# T14_SuperDuper_V_002.net
KiCad netlist of a schematic drawn in EAGLE
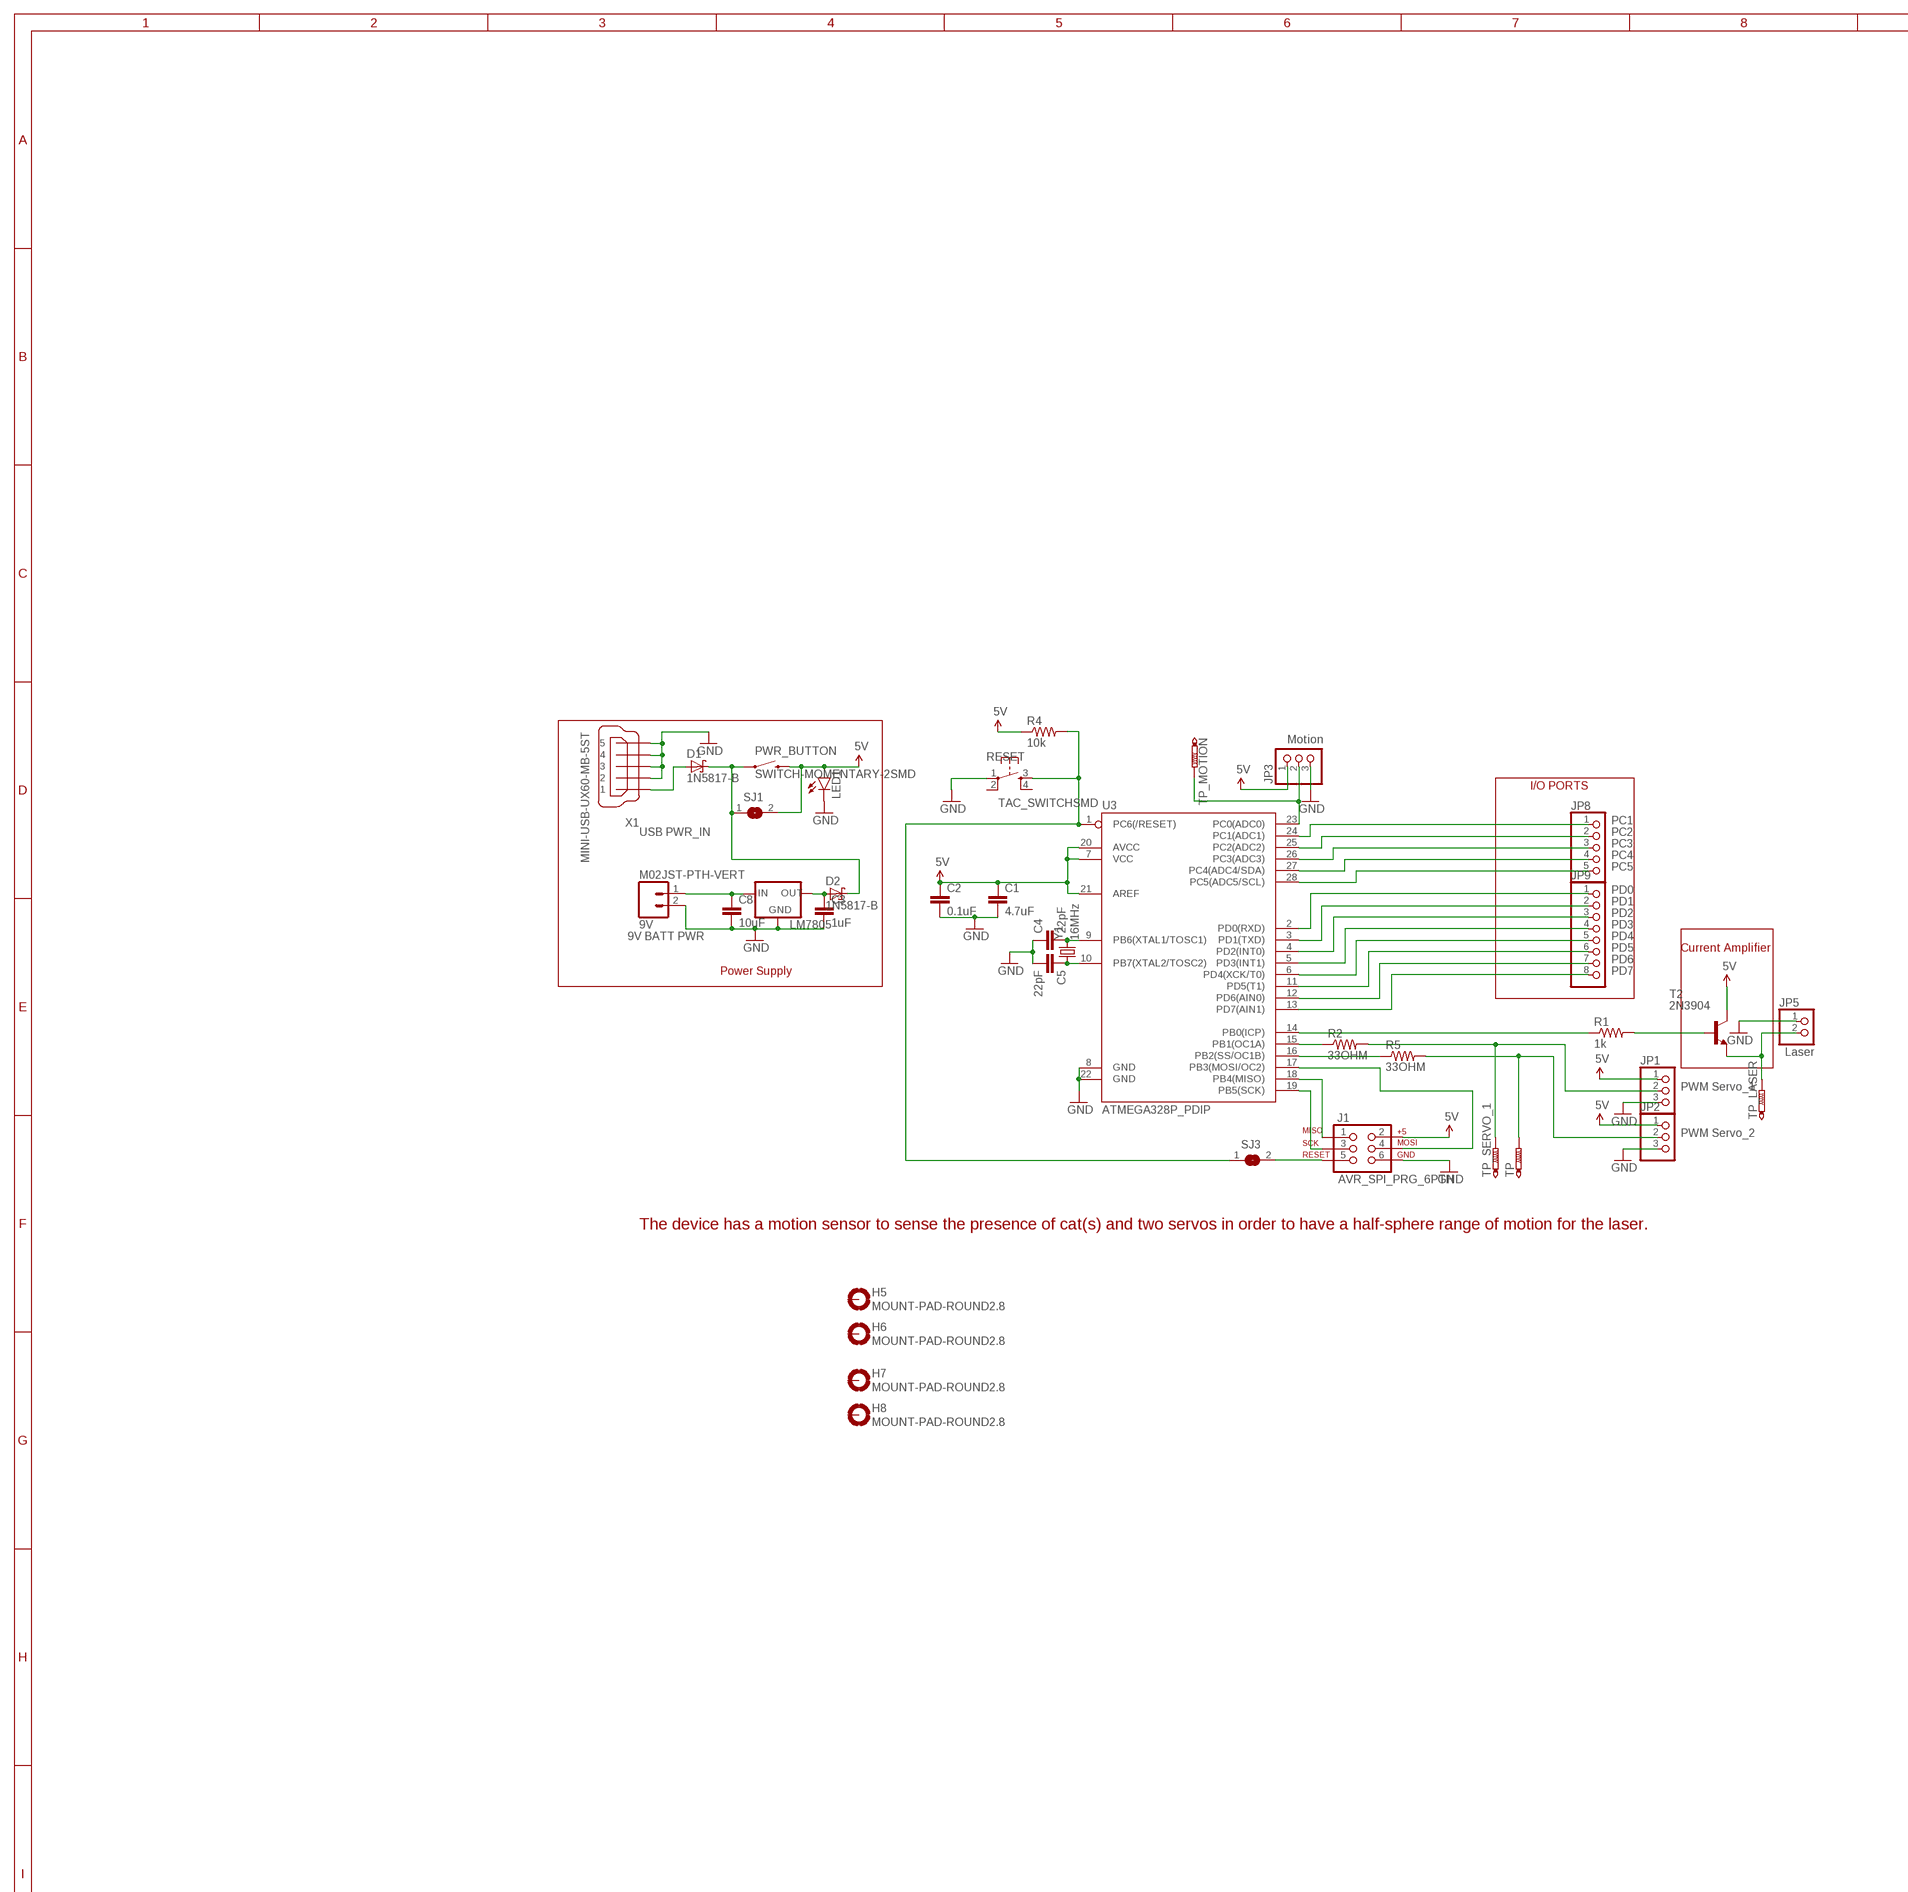
[diagram p0: schematic, sheet 1, part 1 of 2]
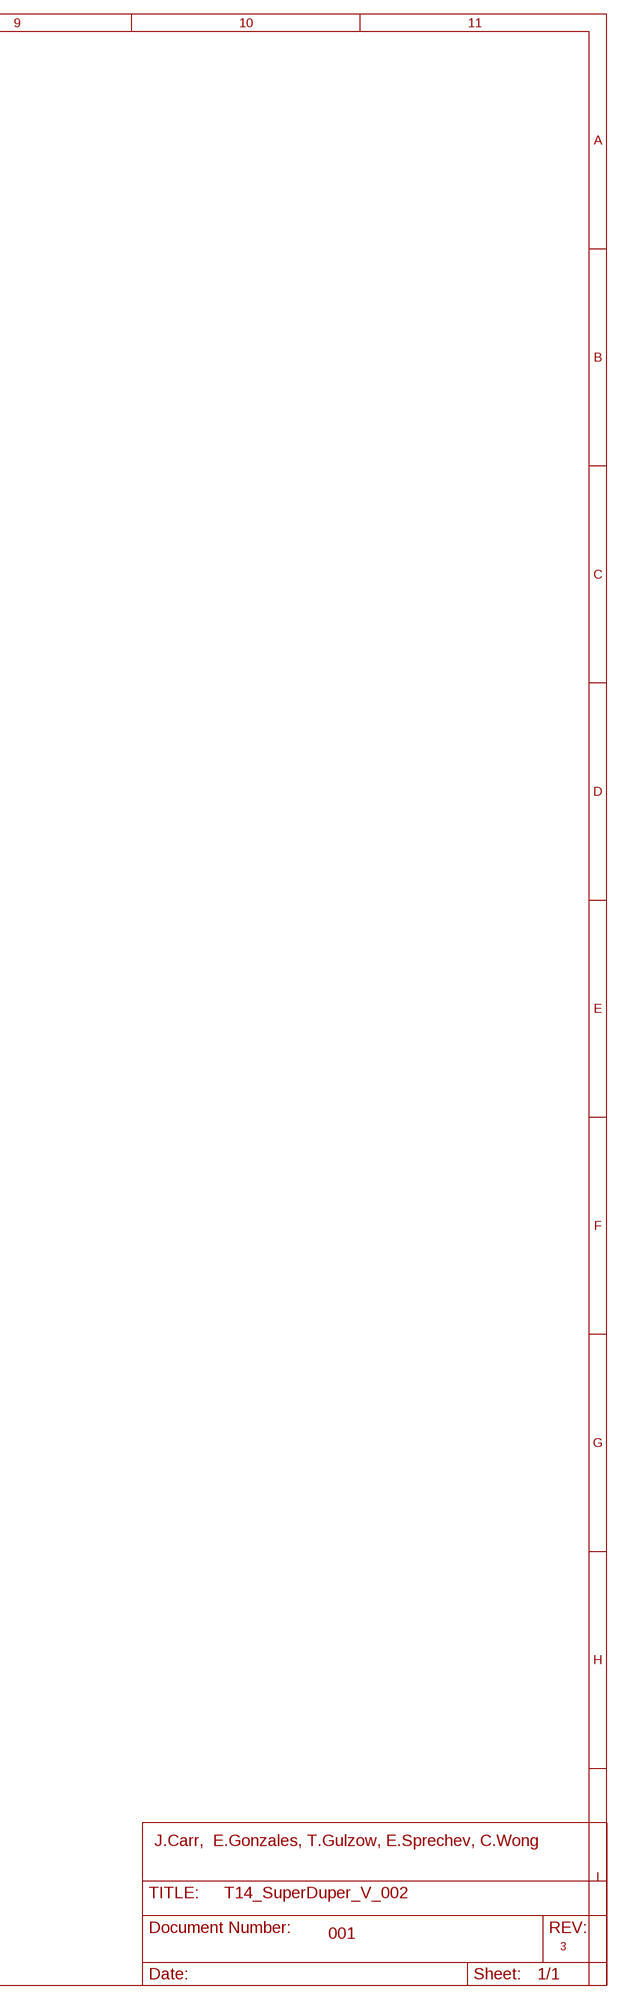
[diagram p1: schematic, sheet 1, part 2 of 2]

(export (version "E")
  (design (tool "Eeschema 10.0.6"))
  (components
    (comp (ref "9V")
      (value "M02JST-PTH-VERT")
      (footprint "eagle-import:JST-2-PTH-VERT")
      (libsource (lib "eagle-import") (part "M02JST-PTH-VERT"))
    )
    (comp (ref "C1")
      (value "4.7uF")
      (footprint "eagle-import:0603-CAP")
      (libsource (lib "eagle-import") (part "4.7UF-6.3V-10%(0603)0603"))
    )
    (comp (ref "C2")
      (value "0.1uF")
      (footprint "eagle-import:0603-CAP")
      (libsource (lib "eagle-import") (part "0.1UF-25V(+80/-20%)(0603)"))
    )
    (comp (ref "C3")
      (value "1uF")
      (footprint "eagle-import:0603-CAP")
      (fields (field (name "PROD_ID") "CAP-00810"))
      (libsource (lib "eagle-import") (part "0.1UF-25V(+80/-20%)(0603)"))
    )
    (comp (ref "C4")
      (value "22pF")
      (footprint "eagle-import:0603-CAP")
      (libsource (lib "eagle-import") (part "4.7UF-6.3V-10%(0603)0603"))
    )
    (comp (ref "C5")
      (value "22pF")
      (footprint "eagle-import:0603-CAP")
      (libsource (lib "eagle-import") (part "4.7UF-6.3V-10%(0603)0603"))
    )
    (comp (ref "C8")
      (value "10uF")
      (footprint "eagle-import:0603-CAP")
      (fields (field (name "PROD_ID") "CAP-00810"))
      (libsource (lib "eagle-import") (part "0.1UF-25V(+80/-20%)(0603)"))
    )
    (comp (ref "D1")
      (value "1N5817-B")
      (footprint "eagle-import:DO41-7.6")
      (libsource (lib "eagle-import") (part "1N5817-B"))
    )
    (comp (ref "D2")
      (value "1N5817-B")
      (footprint "eagle-import:DO41-7.6")
      (libsource (lib "eagle-import") (part "1N5817-B"))
    )
    (comp (ref "H5")
      (value "MOUNT-PAD-ROUND2.8")
      (footprint "eagle-import:2,8-PAD")
      (libsource (lib "eagle-import") (part "MOUNT-PAD-ROUND2.8"))
    )
    (comp (ref "H6")
      (value "MOUNT-PAD-ROUND2.8")
      (footprint "eagle-import:2,8-PAD")
      (libsource (lib "eagle-import") (part "MOUNT-PAD-ROUND2.8"))
    )
    (comp (ref "H7")
      (value "MOUNT-PAD-ROUND2.8")
      (footprint "eagle-import:2,8-PAD")
      (libsource (lib "eagle-import") (part "MOUNT-PAD-ROUND2.8"))
    )
    (comp (ref "H8")
      (value "MOUNT-PAD-ROUND2.8")
      (footprint "eagle-import:2,8-PAD")
      (libsource (lib "eagle-import") (part "MOUNT-PAD-ROUND2.8"))
    )
    (comp (ref "J1")
      (value "AVR_SPI_PRG_6PTH")
      (footprint "eagle-import:2X3")
      (libsource (lib "eagle-import") (part "AVR_SPI_PRG_6PTH"))
    )
    (comp (ref "JP1")
      (value "PINHD-1X3")
      (footprint "eagle-import:1X03")
      (libsource (lib "eagle-import") (part "PINHD-1X3"))
    )
    (comp (ref "JP2")
      (value "PINHD-1X3")
      (footprint "eagle-import:1X03")
      (libsource (lib "eagle-import") (part "PINHD-1X3"))
    )
    (comp (ref "JP3")
      (value "PINHD-1X3")
      (footprint "eagle-import:1X03")
      (libsource (lib "eagle-import") (part "PINHD-1X3"))
    )
    (comp (ref "JP5")
      (value "PINHD-1X2")
      (footprint "eagle-import:1X02")
      (libsource (lib "eagle-import") (part "PINHD-1X2"))
    )
    (comp (ref "JP8")
      (value "PINHD-1X5")
      (footprint "eagle-import:1X05")
      (libsource (lib "eagle-import") (part "PINHD-1X5"))
    )
    (comp (ref "JP9")
      (value "PINHD-1X8")
      (footprint "eagle-import:1X08")
      (libsource (lib "eagle-import") (part "PINHD-1X8"))
    )
    (comp (ref "LED1")
      (value "LED-3MM-NO_SILK")
      (footprint "eagle-import:LED3MM-NS")
      (libsource (lib "eagle-import") (part "LED-3MM-NO_SILK"))
    )
    (comp (ref "LM7805")
      (value "V_REG_78XXSIDE")
      (footprint "eagle-import:78XXL")
      (libsource (lib "eagle-import") (part "V_REG_78XXSIDE"))
    )
    (comp (ref "PWR_BUTTON")
      (value "SWITCH-MOMENTARY-2SMD")
      (footprint "eagle-import:TACTILE-SWITCH-SMD")
      (libsource (lib "eagle-import") (part "SWITCH-MOMENTARY-2SMD"))
    )
    (comp (ref "R1")
      (value "1k")
      (footprint "eagle-import:0603")
      (libsource (lib "eagle-import") (part "33OHM1/10W1%(0603)"))
    )
    (comp (ref "R2")
      (value "33OHM")
      (footprint "eagle-import:0603")
      (libsource (lib "eagle-import") (part "33OHM1/10W1%(0603)"))
    )
    (comp (ref "R4")
      (value "10k")
      (footprint "eagle-import:0603")
      (libsource (lib "eagle-import") (part "33OHM1/10W1%(0603)"))
    )
    (comp (ref "R5")
      (value "33OHM")
      (footprint "eagle-import:0603")
      (libsource (lib "eagle-import") (part "33OHM1/10W1%(0603)"))
    )
    (comp (ref "RESET")
      (value "TAC_SWITCHSMD")
      (footprint "eagle-import:TACTILE-SWITCH-SMD")
      (libsource (lib "eagle-import") (part "TAC_SWITCHSMD"))
    )
    (comp (ref "SJ1") (value "SJ") (footprint "eagle-import:SJ") (libsource (lib "eagle-import") (part "SJ")))
    (comp (ref "SJ3") (value "SJ") (footprint "eagle-import:SJ") (libsource (lib "eagle-import") (part "SJ")))
    (comp (ref "T2")
      (value "2N3904")
      (footprint "eagle-import:TO92")
      (libsource (lib "eagle-import") (part "2N3904"))
    )
    (comp (ref "TP")
      (value "PTR1B2,54")
      (footprint "eagle-import:B2,54")
      (libsource (lib "eagle-import") (part "PTR1B2,54"))
    )
    (comp (ref "TP_LASER")
      (value "PTR1B2,54")
      (footprint "eagle-import:B2,54")
      (libsource (lib "eagle-import") (part "PTR1B2,54"))
    )
    (comp (ref "TP_MOTION")
      (value "PTR1B2,54")
      (footprint "eagle-import:B2,54")
      (libsource (lib "eagle-import") (part "PTR1B2,54"))
    )
    (comp (ref "TP_SERVO_1")
      (value "PTR1B2,54")
      (footprint "eagle-import:B2,54")
      (libsource (lib "eagle-import") (part "PTR1B2,54"))
    )
    (comp (ref "U3")
      (value "ATMEGA328P_PDIP")
      (footprint "eagle-import:DIL28-3")
      (libsource (lib "eagle-import") (part "ATMEGA328P_PDIP"))
    )
    (comp (ref "X1")
      (value "MINI-USB-UX60-MB-5ST")
      (footprint "eagle-import:UX60-MB-5ST")
      (libsource (lib "eagle-import") (part "MINI-USB-UX60-MB-5ST"))
    )
    (comp (ref "Y1")
      (value "16MHz")
      (footprint "eagle-import:CRYSTAL-SMD-10.5X4.8-2PIN")
      (libsource (lib "eagle-import") (part "CRYSTAL10.5X4.8"))
    )
  )
  (nets
    (net (code "1") (name "5V") (class "Default")
      (node (ref "C1") (pin "1") (pinfunction "1_1") (pintype "passive"))
      (node (ref "C2") (pin "1") (pinfunction "1_1") (pintype "passive"))
      (node (ref "J1") (pin "2") (pinfunction "2_2") (pintype "passive"))
      (node (ref "JP1") (pin "1") (pinfunction "1_1") (pintype "passive"))
      (node (ref "JP2") (pin "1") (pinfunction "1_1") (pintype "passive"))
      (node (ref "JP3") (pin "1") (pinfunction "1_1") (pintype "passive"))
      (node (ref "LED1") (pin "A") (pinfunction "A_A") (pintype "passive"))
      (node (ref "PWR_BUTTON") (pin "3") (pinfunction "2_3") (pintype "passive"))
      (node (ref "R4") (pin "1") (pinfunction "1_1") (pintype "passive"))
      (node (ref "SJ1") (pin "2") (pinfunction "2_2") (pintype "passive"))
      (node (ref "T2") (pin "1") (pinfunction "C_1") (pintype "passive"))
      (node (ref "U3") (pin "20") (pinfunction "AVCC_20") (pintype "bidirectional"))
      (node (ref "U3") (pin "21") (pinfunction "AREF_21") (pintype "bidirectional"))
      (node (ref "U3") (pin "7") (pinfunction "VCC_7") (pintype "bidirectional"))
    )
    (net (code "2") (name "GND") (class "Default")
      (node (ref "9V") (pin "2") (pinfunction "2_2") (pintype "passive"))
      (node (ref "C1") (pin "2") (pinfunction "2_2") (pintype "passive"))
      (node (ref "C2") (pin "2") (pinfunction "2_2") (pintype "passive"))
      (node (ref "C3") (pin "2") (pinfunction "2_2") (pintype "passive"))
      (node (ref "C4") (pin "1") (pinfunction "1_1") (pintype "passive"))
      (node (ref "C5") (pin "2") (pinfunction "2_2") (pintype "passive"))
      (node (ref "C8") (pin "2") (pinfunction "2_2") (pintype "passive"))
      (node (ref "J1") (pin "6") (pinfunction "6_6") (pintype "passive"))
      (node (ref "JP1") (pin "3") (pinfunction "3_3") (pintype "passive"))
      (node (ref "JP2") (pin "3") (pinfunction "3_3") (pintype "passive"))
      (node (ref "JP3") (pin "3") (pinfunction "3_3") (pintype "passive"))
      (node (ref "JP5") (pin "1") (pinfunction "1_1") (pintype "passive"))
      (node (ref "LED1") (pin "K") (pinfunction "C_K") (pintype "passive"))
      (node (ref "LM7805") (pin "GND") (pinfunction "GND_GND") (pintype "input"))
      (node (ref "RESET") (pin "1") (pinfunction "1_1") (pintype "passive"))
      (node (ref "U3") (pin "22") (pinfunction "GND_22") (pintype "bidirectional"))
      (node (ref "U3") (pin "8") (pinfunction "GND_8") (pintype "bidirectional"))
      (node (ref "X1") (pin "2") (pinfunction "2_2") (pintype "input"))
      (node (ref "X1") (pin "3") (pinfunction "3_3") (pintype "input"))
      (node (ref "X1") (pin "4") (pinfunction "4_4") (pintype "input"))
      (node (ref "X1") (pin "5") (pinfunction "5_5") (pintype "input"))
    )
    (net (code "3") (name "Net-(9V-Pad1)") (class "Default")
      (node (ref "9V") (pin "1") (pinfunction "1_1") (pintype "passive"))
      (node (ref "C8") (pin "1") (pinfunction "1_1") (pintype "passive"))
      (node (ref "LM7805") (pin "IN") (pinfunction "IN_IN") (pintype "input"))
    )
    (net (code "4") (name "Net-(C3-Pad1)") (class "Default")
      (node (ref "C3") (pin "1") (pinfunction "1_1") (pintype "passive"))
      (node (ref "D2") (pin "A") (pinfunction "A_A") (pintype "passive"))
      (node (ref "LM7805") (pin "OUT") (pinfunction "OUT_OUT") (pintype "output"))
    )
    (net (code "5") (name "Net-(D1-PadA)") (class "Default")
      (node (ref "D1") (pin "A") (pinfunction "A_A") (pintype "passive"))
      (node (ref "X1") (pin "1") (pinfunction "1_1") (pintype "input"))
    )
    (net (code "6") (name "Net-(D1-PadC)") (class "Default")
      (node (ref "D1") (pin "C") (pinfunction "C_C") (pintype "passive"))
      (node (ref "D2") (pin "C") (pinfunction "C_C") (pintype "passive"))
      (node (ref "PWR_BUTTON") (pin "1") (pinfunction "1_1") (pintype "passive"))
      (node (ref "SJ1") (pin "1") (pinfunction "1_1") (pintype "passive"))
    )
    (net (code "7") (name "Net-(J1-Pad5)") (class "Default")
      (node (ref "J1") (pin "5") (pinfunction "5_5") (pintype "passive"))
      (node (ref "SJ3") (pin "2") (pinfunction "2_2") (pintype "passive"))
    )
    (net (code "8") (name "Net-(JP1-Pad2)") (class "Default")
      (node (ref "JP1") (pin "2") (pinfunction "2_2") (pintype "passive"))
      (node (ref "R2") (pin "2") (pinfunction "2_2") (pintype "passive"))
      (node (ref "TP_SERVO_1") (pin "TP") (pinfunction "TP_TP") (pintype "input"))
    )
    (net (code "9") (name "Net-(JP2-Pad2)") (class "Default")
      (node (ref "JP2") (pin "2") (pinfunction "2_2") (pintype "passive"))
      (node (ref "R5") (pin "2") (pinfunction "2_2") (pintype "passive"))
      (node (ref "TP") (pin "TP") (pinfunction "TP_TP") (pintype "input"))
    )
    (net (code "10") (name "Net-(T2-B)") (class "Default")
      (node (ref "R1") (pin "2") (pinfunction "2_2") (pintype "passive"))
      (node (ref "T2") (pin "2") (pinfunction "B_2") (pintype "passive"))
    )
    (net (code "11") (name "Net-(T2-E)") (class "Default")
      (node (ref "JP5") (pin "2") (pinfunction "2_2") (pintype "passive"))
      (node (ref "T2") (pin "3") (pinfunction "E_3") (pintype "passive"))
      (node (ref "TP_LASER") (pin "TP") (pinfunction "TP_TP") (pintype "input"))
    )
    (net (code "12") (name "Net-(U3-PB0(ICP))") (class "Default")
      (node (ref "R1") (pin "1") (pinfunction "1_1") (pintype "passive"))
      (node (ref "U3") (pin "14") (pinfunction "PB0(ICP)_14") (pintype "bidirectional"))
    )
    (net (code "13") (name "Net-(U3-PB1(OC1A))") (class "Default")
      (node (ref "R2") (pin "1") (pinfunction "1_1") (pintype "passive"))
      (node (ref "U3") (pin "15") (pinfunction "PB1(OC1A)_15") (pintype "bidirectional"))
    )
    (net (code "14") (name "Net-(U3-PB2(SS{slash}OC1B))") (class "Default")
      (node (ref "R5") (pin "1") (pinfunction "1_1") (pintype "passive"))
      (node (ref "U3") (pin "16") (pinfunction "PB2(SS/OC1B)_16") (pintype "bidirectional"))
    )
    (net (code "15") (name "Net-(U3-PB3(MOSI{slash}OC2))") (class "Default")
      (node (ref "J1") (pin "4") (pinfunction "4_4") (pintype "passive"))
      (node (ref "U3") (pin "17") (pinfunction "PB3(MOSI/OC2)_17") (pintype "bidirectional"))
    )
    (net (code "16") (name "Net-(U3-PB4(MISO))") (class "Default")
      (node (ref "J1") (pin "1") (pinfunction "1_1") (pintype "passive"))
      (node (ref "U3") (pin "18") (pinfunction "PB4(MISO)_18") (pintype "bidirectional"))
    )
    (net (code "17") (name "Net-(U3-PB5(SCK))") (class "Default")
      (node (ref "J1") (pin "3") (pinfunction "3_3") (pintype "passive"))
      (node (ref "U3") (pin "19") (pinfunction "PB5(SCK)_19") (pintype "bidirectional"))
    )
    (net (code "18") (name "Net-(U3-PB6(XTAL1{slash}TOSC1))") (class "Default")
      (node (ref "C4") (pin "2") (pinfunction "2_2") (pintype "passive"))
      (node (ref "U3") (pin "9") (pinfunction "PB6(XTAL1/TOSC1)_9") (pintype "bidirectional"))
      (node (ref "Y1") (pin "P$2") (pinfunction "2_P$2") (pintype "passive"))
    )
    (net (code "19") (name "Net-(U3-PB7(XTAL2{slash}TOSC2))") (class "Default")
      (node (ref "C5") (pin "1") (pinfunction "1_1") (pintype "passive"))
      (node (ref "U3") (pin "10") (pinfunction "PB7(XTAL2/TOSC2)_10") (pintype "bidirectional"))
      (node (ref "Y1") (pin "P$1") (pinfunction "1_P$1") (pintype "passive"))
    )
    (net (code "20") (name "Net-(U3-PC0(ADC0))") (class "Default")
      (node (ref "JP3") (pin "2") (pinfunction "2_2") (pintype "passive"))
      (node (ref "TP_MOTION") (pin "TP") (pinfunction "TP_TP") (pintype "input"))
      (node (ref "U3") (pin "23") (pinfunction "PC0(ADC0)_23") (pintype "bidirectional"))
    )
    (net (code "21") (name "Net-(U3-PC1(ADC1))") (class "Default")
      (node (ref "JP8") (pin "1") (pinfunction "1_1") (pintype "passive"))
      (node (ref "U3") (pin "24") (pinfunction "PC1(ADC1)_24") (pintype "bidirectional"))
    )
    (net (code "22") (name "Net-(U3-PC2(ADC2))") (class "Default")
      (node (ref "JP8") (pin "2") (pinfunction "2_2") (pintype "passive"))
      (node (ref "U3") (pin "25") (pinfunction "PC2(ADC2)_25") (pintype "bidirectional"))
    )
    (net (code "23") (name "Net-(U3-PC3(ADC3))") (class "Default")
      (node (ref "JP8") (pin "3") (pinfunction "3_3") (pintype "passive"))
      (node (ref "U3") (pin "26") (pinfunction "PC3(ADC3)_26") (pintype "bidirectional"))
    )
    (net (code "24") (name "Net-(U3-PC4(ADC4{slash}SDA))") (class "Default")
      (node (ref "JP8") (pin "4") (pinfunction "4_4") (pintype "passive"))
      (node (ref "U3") (pin "27") (pinfunction "PC4(ADC4/SDA)_27") (pintype "bidirectional"))
    )
    (net (code "25") (name "Net-(U3-PC5(ADC5{slash}SCL))") (class "Default")
      (node (ref "JP8") (pin "5") (pinfunction "5_5") (pintype "passive"))
      (node (ref "U3") (pin "28") (pinfunction "PC5(ADC5/SCL)_28") (pintype "bidirectional"))
    )
    (net (code "26") (name "Net-(U3-PC6({slash}RESET))") (class "Default")
      (node (ref "R4") (pin "2") (pinfunction "2_2") (pintype "passive"))
      (node (ref "RESET") (pin "3") (pinfunction "3_3") (pintype "passive"))
      (node (ref "SJ3") (pin "1") (pinfunction "1_1") (pintype "passive"))
      (node (ref "U3") (pin "1") (pinfunction "PC6(/RESET)_1") (pintype "bidirectional"))
    )
    (net (code "27") (name "Net-(U3-PD0(RXD))") (class "Default")
      (node (ref "JP9") (pin "1") (pinfunction "1_1") (pintype "passive"))
      (node (ref "U3") (pin "2") (pinfunction "PD0(RXD)_2") (pintype "bidirectional"))
    )
    (net (code "28") (name "Net-(U3-PD1(TXD))") (class "Default")
      (node (ref "JP9") (pin "2") (pinfunction "2_2") (pintype "passive"))
      (node (ref "U3") (pin "3") (pinfunction "PD1(TXD)_3") (pintype "bidirectional"))
    )
    (net (code "29") (name "Net-(U3-PD2(INT0))") (class "Default")
      (node (ref "JP9") (pin "3") (pinfunction "3_3") (pintype "passive"))
      (node (ref "U3") (pin "4") (pinfunction "PD2(INT0)_4") (pintype "bidirectional"))
    )
    (net (code "30") (name "Net-(U3-PD3(INT1))") (class "Default")
      (node (ref "JP9") (pin "4") (pinfunction "4_4") (pintype "passive"))
      (node (ref "U3") (pin "5") (pinfunction "PD3(INT1)_5") (pintype "bidirectional"))
    )
    (net (code "31") (name "Net-(U3-PD4(XCK{slash}T0))") (class "Default")
      (node (ref "JP9") (pin "5") (pinfunction "5_5") (pintype "passive"))
      (node (ref "U3") (pin "6") (pinfunction "PD4(XCK/T0)_6") (pintype "bidirectional"))
    )
    (net (code "32") (name "Net-(U3-PD5(T1))") (class "Default")
      (node (ref "JP9") (pin "6") (pinfunction "6_6") (pintype "passive"))
      (node (ref "U3") (pin "11") (pinfunction "PD5(T1)_11") (pintype "bidirectional"))
    )
    (net (code "33") (name "Net-(U3-PD6(AIN0))") (class "Default")
      (node (ref "JP9") (pin "7") (pinfunction "7_7") (pintype "passive"))
      (node (ref "U3") (pin "12") (pinfunction "PD6(AIN0)_12") (pintype "bidirectional"))
    )
    (net (code "34") (name "Net-(U3-PD7(AIN1))") (class "Default")
      (node (ref "JP9") (pin "8") (pinfunction "8_8") (pintype "passive"))
      (node (ref "U3") (pin "13") (pinfunction "PD7(AIN1)_13") (pintype "bidirectional"))
    )
    (net (code "35") (name "unconnected-(H5-MOUNT-PadB2,8)") (class "Default")
      (node (ref "H5") (pin "B2,8") (pinfunction "MOUNT_B2,8") (pintype "passive"))
    )
    (net (code "36") (name "unconnected-(H6-MOUNT-PadB2,8)") (class "Default")
      (node (ref "H6") (pin "B2,8") (pinfunction "MOUNT_B2,8") (pintype "passive"))
    )
    (net (code "37") (name "unconnected-(H7-MOUNT-PadB2,8)") (class "Default")
      (node (ref "H7") (pin "B2,8") (pinfunction "MOUNT_B2,8") (pintype "passive"))
    )
    (net (code "38") (name "unconnected-(H8-MOUNT-PadB2,8)") (class "Default")
      (node (ref "H8") (pin "B2,8") (pinfunction "MOUNT_B2,8") (pintype "passive"))
    )
    (net (code "39") (name "unconnected-(RESET-Pad2)") (class "Default")
      (node (ref "RESET") (pin "2") (pinfunction "2_2") (pintype "passive"))
    )
    (net (code "40") (name "unconnected-(RESET-Pad4)") (class "Default")
      (node (ref "RESET") (pin "4") (pinfunction "4_4") (pintype "passive"))
    )
  )
)
